# MCU.net
KiCad netlist of a schematic drawn in Altium Designer
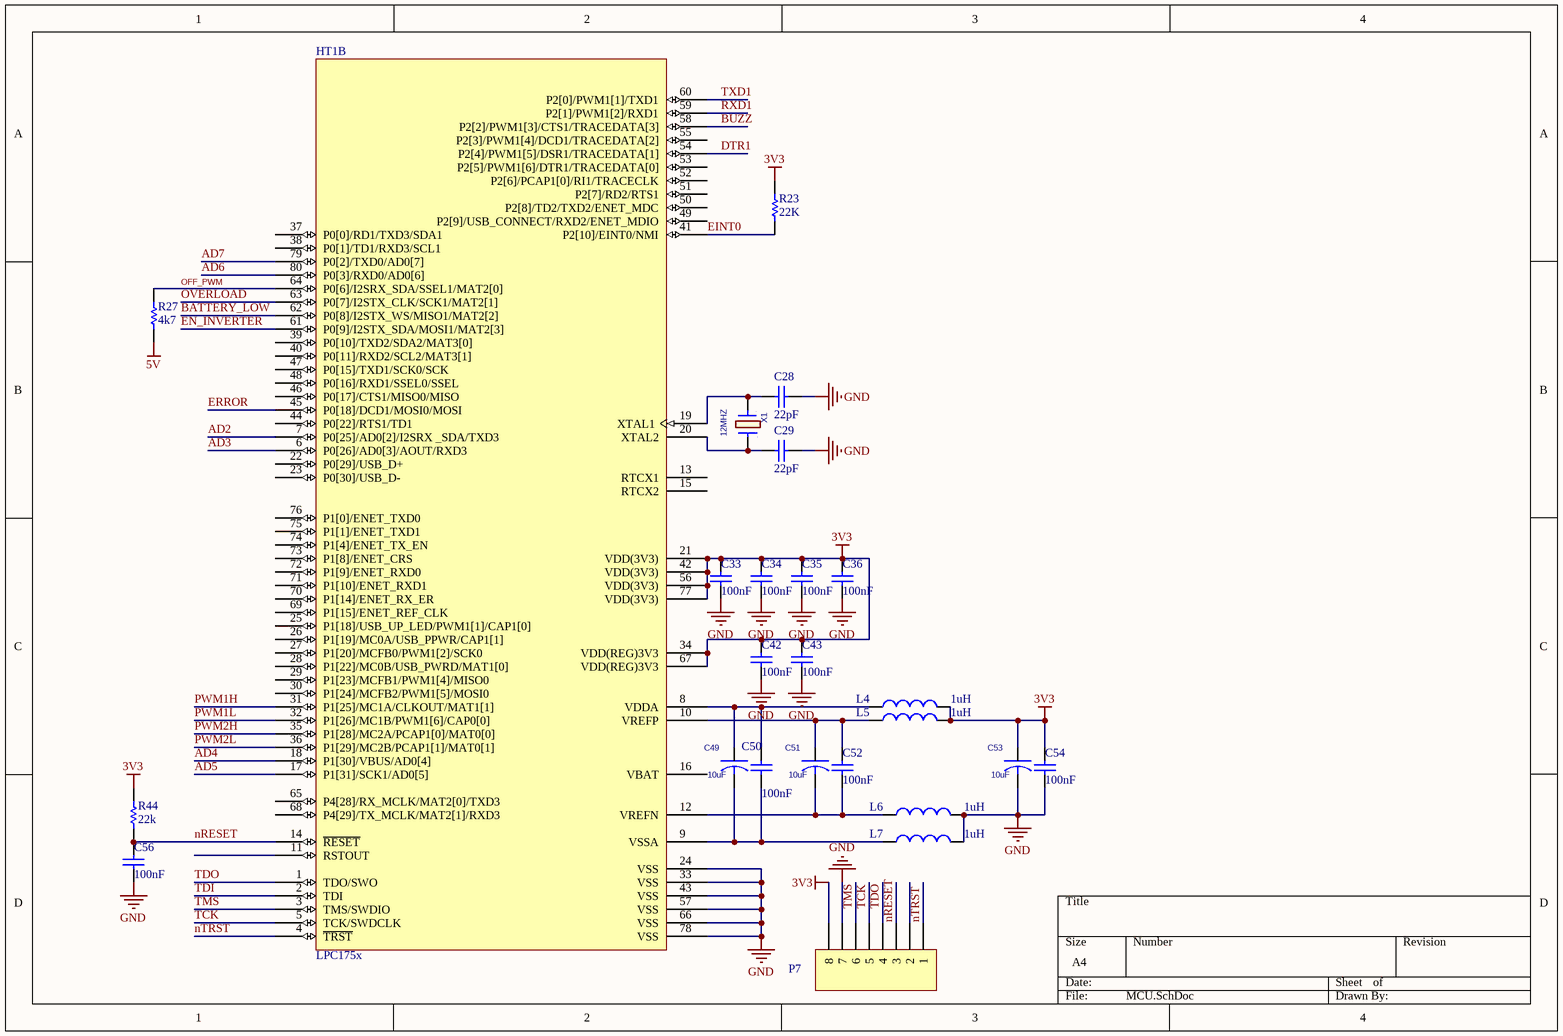
[diagram p0: MCU.SchDoc]

(export (version "E")
  (design (tool "Eeschema 10.0.6"))
  (components
    (comp (ref "C28")
      (value "22pF")
      (footprint "C0805")
      (description "Capacitor Type 0805 SMD")
      (fields (field (name "Comment") "CX4") (field (name "PUBLISHER") "Altium Limited"))
      (libsource (lib "Miscellaneous Devices") (part "Cap"))
    )
    (comp (ref "C29")
      (value "22pF")
      (footprint "C0805")
      (description "Capacitor Type 0805 SMD")
      (fields (field (name "Comment") "CX4") (field (name "PUBLISHER") "Altium Limited"))
      (libsource (lib "Miscellaneous Devices") (part "Cap"))
    )
    (comp (ref "C33")
      (value "100nF")
      (footprint "C0805")
      (description "Capacitor Type 0805 SMD")
      (fields (field (name "Comment") "CX4") (field (name "PUBLISHER") "Altium Limited"))
      (libsource (lib "Miscellaneous Devices") (part "Cap"))
    )
    (comp (ref "C34")
      (value "100nF")
      (footprint "C0805")
      (description "Capacitor Type 0805 SMD")
      (fields (field (name "Comment") "CX4") (field (name "PUBLISHER") "Altium Limited"))
      (libsource (lib "Miscellaneous Devices") (part "Cap"))
    )
    (comp (ref "C35")
      (value "100nF")
      (footprint "C0805")
      (description "Capacitor Type 0805 SMD")
      (fields (field (name "Comment") "CX4") (field (name "PUBLISHER") "Altium Limited"))
      (libsource (lib "Miscellaneous Devices") (part "Cap"))
    )
    (comp (ref "C36")
      (value "100nF")
      (footprint "C0805")
      (description "Capacitor Type 0805 SMD")
      (fields (field (name "Comment") "CX4") (field (name "PUBLISHER") "Altium Limited"))
      (libsource (lib "Miscellaneous Devices") (part "Cap"))
    )
    (comp (ref "C42")
      (value "100nF")
      (footprint "C0805")
      (description "Capacitor Type 0805 SMD")
      (fields (field (name "Comment") "CX4") (field (name "PUBLISHER") "Altium Limited"))
      (libsource (lib "Miscellaneous Devices") (part "Cap"))
    )
    (comp (ref "C43")
      (value "100nF")
      (footprint "C0805")
      (description "Capacitor Type 0805 SMD")
      (fields (field (name "Comment") "CX4") (field (name "PUBLISHER") "Altium Limited"))
      (libsource (lib "Miscellaneous Devices") (part "Cap"))
    )
    (comp (ref "C49") (value "10uF") (footprint "CAP_10uF_SMD") (libsource (lib "*") (part "C")))
    (comp (ref "C50")
      (value "100nF")
      (footprint "C0805")
      (description "Capacitor Type 0805 SMD")
      (fields (field (name "Comment") "CX4") (field (name "PUBLISHER") "Altium Limited"))
      (libsource (lib "Miscellaneous Devices") (part "Cap"))
    )
    (comp (ref "C51") (value "10uF") (footprint "CAP_10uF_SMD") (libsource (lib "*") (part "C")))
    (comp (ref "C52")
      (value "100nF")
      (footprint "C0805")
      (description "Capacitor Type 0805 SMD")
      (fields (field (name "Comment") "CX4") (field (name "PUBLISHER") "Altium Limited"))
      (libsource (lib "Miscellaneous Devices") (part "Cap"))
    )
    (comp (ref "C53") (value "10uF") (footprint "CAP_10uF_SMD") (libsource (lib "*") (part "C")))
    (comp (ref "C54")
      (value "100nF")
      (footprint "C0805")
      (description "Capacitor Type 0805 SMD")
      (fields (field (name "Comment") "CX4") (field (name "PUBLISHER") "Altium Limited"))
      (libsource (lib "Miscellaneous Devices") (part "Cap"))
    )
    (comp (ref "C56")
      (value "100nF")
      (footprint "C0805")
      (description "Capacitor Type 0805 SMD")
      (fields (field (name "Comment") "CX4") (field (name "PUBLISHER") "Altium Limited"))
      (libsource (lib "Miscellaneous Devices") (part "Cap"))
    )
    (comp (ref "HT1")
      (value "LPC175x")
      (footprint "PCBComponent_1 - duplicate")
      (libsource (lib "LPC175x") (part "LPC175x"))
    )
    (comp (ref "L4")
      (value "1uH")
      (footprint "L_1uH")
      (description "Inductor Type 1206 SMD")
      (fields (field (name "Comment") "Inductor") (field (name "PUBLISHER") "Altium Limited"))
      (libsource (lib "Miscellaneous Devices") (part "Inductor"))
    )
    (comp (ref "L5")
      (value "1uH")
      (footprint "L_1uH")
      (description "Inductor Type 1206 SMD")
      (fields (field (name "Comment") "Inductor") (field (name "PUBLISHER") "Altium Limited"))
      (libsource (lib "Miscellaneous Devices") (part "Inductor"))
    )
    (comp (ref "L6")
      (value "1uH")
      (footprint "L_1uH")
      (description "Inductor Type 1206 SMD")
      (fields (field (name "Comment") "Inductor") (field (name "PUBLISHER") "Altium Limited"))
      (libsource (lib "Miscellaneous Devices") (part "Inductor"))
    )
    (comp (ref "L7")
      (value "1uH")
      (footprint "L_1uH")
      (description "Inductor Type 1206 SMD")
      (fields (field (name "Comment") "Inductor") (field (name "PUBLISHER") "Altium Limited"))
      (libsource (lib "Miscellaneous Devices") (part "Inductor"))
    )
    (comp (ref "P7")
      (value "Header 8")
      (footprint "HDR1X8")
      (description "Header, 8-Pin")
      (fields (field (name "PUBLISHER") "Altium Limited"))
      (libsource (lib "Miscellaneous Connectors") (part "Header 8"))
    )
    (comp (ref "R23")
      (value "22K")
      (footprint "R0805")
      (description "Resistor SMD0805")
      (fields (field (name "PUBLISHER") "Altium Limited"))
      (libsource (lib "Miscellaneous Devices") (part "Res1"))
    )
    (comp (ref "R27")
      (value "4k7")
      (footprint "R0805")
      (description "Resistor SMD0805")
      (fields (field (name "PUBLISHER") "Altium Limited"))
      (libsource (lib "Miscellaneous Devices") (part "Res1"))
    )
    (comp (ref "R44")
      (value "22k")
      (footprint "R0805")
      (description "Resistor SMD0805")
      (fields (field (name "PUBLISHER") "Altium Limited"))
      (libsource (lib "Miscellaneous Devices") (part "Res1"))
    )
    (comp (ref "X1")
      (value "12MHZ")
      (footprint "CRYSTAL_12Mhz")
      (description "Thach anh 12MHZ")
      (libsource (lib "*") (part "QZS10MEG_0"))
    )
  )
  (nets
    (net (code "1") (name "/AD2") (class "Default")
      (node (ref "HT1") (pin "7") (pinfunction "P0[25]/AD0[2]/I2SRX__SDA/TXD3_7") (pintype "bidirectional"))
    )
    (net (code "2") (name "/AD3") (class "Default")
      (node (ref "HT1") (pin "6") (pinfunction "P0[26]/AD0[3]/AOUT/RXD3_6") (pintype "bidirectional"))
    )
    (net (code "3") (name "/AD4") (class "Default")
      (node (ref "HT1") (pin "18") (pinfunction "P1[30]/VBUS/AD0[4]_18") (pintype "bidirectional"))
    )
    (net (code "4") (name "/AD5") (class "Default")
      (node (ref "HT1") (pin "17") (pinfunction "P1[31]/SCK1/AD0[5]_17") (pintype "bidirectional"))
    )
    (net (code "5") (name "/AD6") (class "Default")
      (node (ref "HT1") (pin "80") (pinfunction "P0[3]/RXD0/AD0[6]_80") (pintype "bidirectional"))
    )
    (net (code "6") (name "/AD7") (class "Default")
      (node (ref "HT1") (pin "79") (pinfunction "P0[2]/TXD0/AD0[7]_79") (pintype "bidirectional"))
    )
    (net (code "7") (name "/BATTERY_LOW") (class "Default")
      (node (ref "HT1") (pin "62") (pinfunction "P0[8]/I2STX_WS/MISO1/MAT2[2]_62") (pintype "bidirectional"))
    )
    (net (code "8") (name "/BUZZ") (class "Default")
      (node (ref "HT1") (pin "58") (pinfunction "P2[2]/PWM1[3]/CTS1/TRACEDATA[3]_58") (pintype "bidirectional"))
    )
    (net (code "9") (name "/DTR1") (class "Default")
      (node (ref "HT1") (pin "54") (pinfunction "P2[4]/PWM1[5]/DSR1/TRACEDATA[1]_54") (pintype "bidirectional"))
    )
    (net (code "10") (name "/EINT0") (class "Default")
      (node (ref "HT1") (pin "41") (pinfunction "P2[10]/EINT0/NMI_41") (pintype "bidirectional"))
      (node (ref "R23") (pin "1") (pinfunction "1_1") (pintype "passive"))
    )
    (net (code "11") (name "/EN_INVERTER") (class "Default")
      (node (ref "HT1") (pin "61") (pinfunction "P0[9]/I2STX_SDA/MOSI1/MAT2[3]_61") (pintype "bidirectional"))
    )
    (net (code "12") (name "/ERROR") (class "Default")
      (node (ref "HT1") (pin "45") (pinfunction "P0[18]/DCD1/MOSI0/MOSI_45") (pintype "bidirectional"))
    )
    (net (code "13") (name "/OFF_PWM") (class "Default")
      (node (ref "HT1") (pin "64") (pinfunction "P0[6]/I2SRX_SDA/SSEL1/MAT2[0]_64") (pintype "bidirectional"))
      (node (ref "R27") (pin "2") (pinfunction "2_2") (pintype "passive"))
    )
    (net (code "14") (name "/OVERLOAD") (class "Default")
      (node (ref "HT1") (pin "63") (pinfunction "P0[7]/I2STX_CLK/SCK1/MAT2[1]_63") (pintype "bidirectional"))
    )
    (net (code "15") (name "/PWM1H") (class "Default")
      (node (ref "HT1") (pin "31") (pinfunction "P1[25]/MC1A/CLKOUT/MAT1[1]_31") (pintype "bidirectional"))
    )
    (net (code "16") (name "/PWM1L") (class "Default")
      (node (ref "HT1") (pin "32") (pinfunction "P1[26]/MC1B/PWM1[6]/CAP0[0]_32") (pintype "bidirectional"))
    )
    (net (code "17") (name "/PWM2H") (class "Default")
      (node (ref "HT1") (pin "35") (pinfunction "P1[28]/MC2A/PCAP1[0]/MAT0[0]_35") (pintype "bidirectional"))
    )
    (net (code "18") (name "/PWM2L") (class "Default")
      (node (ref "HT1") (pin "36") (pinfunction "P1[29]/MC2B/PCAP1[1]/MAT0[1]_36") (pintype "bidirectional"))
    )
    (net (code "19") (name "/RXD1") (class "Default")
      (node (ref "HT1") (pin "59") (pinfunction "P2[1]/PWM1[2]/RXD1_59") (pintype "bidirectional"))
    )
    (net (code "20") (name "/TCK") (class "Default")
      (node (ref "HT1") (pin "5") (pinfunction "TCK/SWDCLK_5") (pintype "bidirectional"))
      (node (ref "P7") (pin "5") (pinfunction "5_5") (pintype "passive"))
    )
    (net (code "21") (name "/TDI") (class "Default")
      (node (ref "HT1") (pin "2") (pinfunction "TDI_2") (pintype "bidirectional"))
    )
    (net (code "22") (name "/TDO") (class "Default")
      (node (ref "HT1") (pin "1") (pinfunction "TDO/SWO_1") (pintype "bidirectional"))
      (node (ref "P7") (pin "4") (pinfunction "4_4") (pintype "passive"))
    )
    (net (code "23") (name "/TMS") (class "Default")
      (node (ref "HT1") (pin "3") (pinfunction "TMS/SWDIO_3") (pintype "bidirectional"))
      (node (ref "P7") (pin "6") (pinfunction "6_6") (pintype "passive"))
    )
    (net (code "24") (name "/TXD1") (class "Default")
      (node (ref "HT1") (pin "60") (pinfunction "P2[0]/PWM1[1]/TXD1_60") (pintype "bidirectional"))
    )
    (net (code "25") (name "/nRESET") (class "Default")
      (node (ref "C56") (pin "2") (pinfunction "2_2") (pintype "passive"))
      (node (ref "HT1") (pin "14") (pinfunction "~{RESET}_14") (pintype "bidirectional"))
      (node (ref "P7") (pin "3") (pinfunction "3_3") (pintype "passive"))
      (node (ref "R44") (pin "1") (pinfunction "1_1") (pintype "passive"))
    )
    (net (code "26") (name "/nTRST") (class "Default")
      (node (ref "HT1") (pin "4") (pinfunction "~{TRST}_4") (pintype "bidirectional"))
      (node (ref "P7") (pin "1") (pinfunction "1_1") (pintype "passive"))
    )
    (net (code "27") (name "3V3") (class "Default")
      (node (ref "C33") (pin "2") (pinfunction "2_2") (pintype "passive"))
      (node (ref "C34") (pin "2") (pinfunction "2_2") (pintype "passive"))
      (node (ref "C35") (pin "2") (pinfunction "2_2") (pintype "passive"))
      (node (ref "C36") (pin "2") (pinfunction "2_2") (pintype "passive"))
      (node (ref "C42") (pin "2") (pinfunction "2_2") (pintype "passive"))
      (node (ref "C43") (pin "2") (pinfunction "2_2") (pintype "passive"))
      (node (ref "C53") (pin "1") (pinfunction "1_1") (pintype "passive"))
      (node (ref "C54") (pin "2") (pinfunction "2_2") (pintype "passive"))
      (node (ref "HT1") (pin "21") (pinfunction "VDD(3V3)_21") (pintype "power_in"))
      (node (ref "HT1") (pin "34") (pinfunction "VDD(REG)3V3_34") (pintype "power_in"))
      (node (ref "HT1") (pin "42") (pinfunction "VDD(3V3)_42") (pintype "power_in"))
      (node (ref "HT1") (pin "56") (pinfunction "VDD(3V3)_56") (pintype "power_in"))
      (node (ref "HT1") (pin "67") (pinfunction "VDD(REG)3V3_67") (pintype "power_in"))
      (node (ref "HT1") (pin "77") (pinfunction "VDD(3V3)_77") (pintype "power_in"))
      (node (ref "L4") (pin "2") (pinfunction "2_2") (pintype "passive"))
      (node (ref "L5") (pin "2") (pinfunction "2_2") (pintype "passive"))
      (node (ref "P7") (pin "8") (pinfunction "8_8") (pintype "passive"))
      (node (ref "R23") (pin "2") (pinfunction "2_2") (pintype "passive"))
      (node (ref "R44") (pin "2") (pinfunction "2_2") (pintype "passive"))
    )
    (net (code "28") (name "5V") (class "Default")
      (node (ref "R27") (pin "1") (pinfunction "1_1") (pintype "passive"))
    )
    (net (code "29") (name "GND") (class "Default")
      (node (ref "C28") (pin "1") (pinfunction "1_1") (pintype "passive"))
      (node (ref "C29") (pin "1") (pinfunction "1_1") (pintype "passive"))
      (node (ref "C33") (pin "1") (pinfunction "1_1") (pintype "passive"))
      (node (ref "C34") (pin "1") (pinfunction "1_1") (pintype "passive"))
      (node (ref "C35") (pin "1") (pinfunction "1_1") (pintype "passive"))
      (node (ref "C36") (pin "1") (pinfunction "1_1") (pintype "passive"))
      (node (ref "C42") (pin "1") (pinfunction "1_1") (pintype "passive"))
      (node (ref "C43") (pin "1") (pinfunction "1_1") (pintype "passive"))
      (node (ref "C53") (pin "2") (pinfunction "2_2") (pintype "passive"))
      (node (ref "C54") (pin "1") (pinfunction "1_1") (pintype "passive"))
      (node (ref "C56") (pin "1") (pinfunction "1_1") (pintype "passive"))
      (node (ref "HT1") (pin "24") (pinfunction "VSS_24") (pintype "power_in"))
      (node (ref "HT1") (pin "33") (pinfunction "VSS_33") (pintype "power_in"))
      (node (ref "HT1") (pin "43") (pinfunction "VSS_43") (pintype "power_in"))
      (node (ref "HT1") (pin "57") (pinfunction "VSS_57") (pintype "power_in"))
      (node (ref "HT1") (pin "66") (pinfunction "VSS_66") (pintype "power_in"))
      (node (ref "HT1") (pin "78") (pinfunction "VSS_78") (pintype "power_in"))
      (node (ref "L6") (pin "2") (pinfunction "2_2") (pintype "passive"))
      (node (ref "L7") (pin "2") (pinfunction "2_2") (pintype "passive"))
      (node (ref "P7") (pin "7") (pinfunction "7_7") (pintype "passive"))
    )
    (net (code "30") (name "Net-(HT1B-VDDA)") (class "Default")
      (node (ref "C49") (pin "1") (pinfunction "1_1") (pintype "passive"))
      (node (ref "C50") (pin "2") (pinfunction "2_2") (pintype "passive"))
      (node (ref "HT1") (pin "8") (pinfunction "VDDA_8") (pintype "power_in"))
      (node (ref "L4") (pin "1") (pinfunction "1_1") (pintype "passive"))
    )
    (net (code "31") (name "Net-(HT1B-VREFN)") (class "Default")
      (node (ref "C51") (pin "2") (pinfunction "2_2") (pintype "passive"))
      (node (ref "C52") (pin "1") (pinfunction "1_1") (pintype "passive"))
      (node (ref "HT1") (pin "12") (pinfunction "VREFN_12") (pintype "power_in"))
      (node (ref "L6") (pin "1") (pinfunction "1_1") (pintype "passive"))
    )
    (net (code "32") (name "Net-(HT1B-VREFP)") (class "Default")
      (node (ref "C51") (pin "1") (pinfunction "1_1") (pintype "passive"))
      (node (ref "C52") (pin "2") (pinfunction "2_2") (pintype "passive"))
      (node (ref "HT1") (pin "10") (pinfunction "VREFP_10") (pintype "power_in"))
      (node (ref "L5") (pin "1") (pinfunction "1_1") (pintype "passive"))
    )
    (net (code "33") (name "Net-(HT1B-VSSA)") (class "Default")
      (node (ref "C49") (pin "2") (pinfunction "2_2") (pintype "passive"))
      (node (ref "C50") (pin "1") (pinfunction "1_1") (pintype "passive"))
      (node (ref "HT1") (pin "9") (pinfunction "VSSA_9") (pintype "power_in"))
      (node (ref "L7") (pin "1") (pinfunction "1_1") (pintype "passive"))
    )
    (net (code "34") (name "Net-(HT1B-XTAL1)") (class "Default")
      (node (ref "C28") (pin "2") (pinfunction "2_2") (pintype "passive"))
      (node (ref "HT1") (pin "19") (pinfunction "XTAL1_19") (pintype "input"))
      (node (ref "X1") (pin "1") (pinfunction "1_1") (pintype "passive"))
    )
    (net (code "35") (name "Net-(HT1B-XTAL2)") (class "Default")
      (node (ref "C29") (pin "2") (pinfunction "2_2") (pintype "passive"))
      (node (ref "HT1") (pin "20") (pinfunction "XTAL2_20") (pintype "passive"))
      (node (ref "X1") (pin "2") (pinfunction "2_2") (pintype "passive"))
    )
    (net (code "36") (name "unconnected-(HT1B-P0[0]{slash}RD1{slash}TXD3{slash}SDA1-Pad37)") (class "Default")
      (node (ref "HT1") (pin "37") (pinfunction "P0[0]/RD1/TXD3/SDA1_37") (pintype "bidirectional"))
    )
    (net (code "37") (name "unconnected-(HT1B-P0[1]{slash}TD1{slash}RXD3{slash}SCL1-Pad38)") (class "Default")
      (node (ref "HT1") (pin "38") (pinfunction "P0[1]/TD1/RXD3/SCL1_38") (pintype "bidirectional"))
    )
    (net (code "38") (name "unconnected-(HT1B-P0[10]{slash}TXD2{slash}SDA2{slash}MAT3[0]-Pad39)") (class "Default")
      (node (ref "HT1") (pin "39") (pinfunction "P0[10]/TXD2/SDA2/MAT3[0]_39") (pintype "bidirectional"))
    )
    (net (code "39") (name "unconnected-(HT1B-P0[11]{slash}RXD2{slash}SCL2{slash}MAT3[1]-Pad40)") (class "Default")
      (node (ref "HT1") (pin "40") (pinfunction "P0[11]/RXD2/SCL2/MAT3[1]_40") (pintype "bidirectional"))
    )
    (net (code "40") (name "unconnected-(HT1B-P0[15]{slash}TXD1{slash}SCK0{slash}SCK-Pad47)") (class "Default")
      (node (ref "HT1") (pin "47") (pinfunction "P0[15]/TXD1/SCK0/SCK_47") (pintype "bidirectional"))
    )
    (net (code "41") (name "unconnected-(HT1B-P0[16]{slash}RXD1{slash}SSEL0{slash}SSEL-Pad48)") (class "Default")
      (node (ref "HT1") (pin "48") (pinfunction "P0[16]/RXD1/SSEL0/SSEL_48") (pintype "bidirectional"))
    )
    (net (code "42") (name "unconnected-(HT1B-P0[17]{slash}CTS1{slash}MISO0{slash}MISO-Pad46)") (class "Default")
      (node (ref "HT1") (pin "46") (pinfunction "P0[17]/CTS1/MISO0/MISO_46") (pintype "bidirectional"))
    )
    (net (code "43") (name "unconnected-(HT1B-P0[22]{slash}RTS1{slash}TD1-Pad44)") (class "Default")
      (node (ref "HT1") (pin "44") (pinfunction "P0[22]/RTS1/TD1_44") (pintype "bidirectional"))
    )
    (net (code "44") (name "unconnected-(HT1B-P0[29]{slash}USB_D+-Pad22)") (class "Default")
      (node (ref "HT1") (pin "22") (pinfunction "P0[29]/USB_D+_22") (pintype "bidirectional"))
    )
    (net (code "45") (name "unconnected-(HT1B-P0[30]{slash}USB_D--Pad23)") (class "Default")
      (node (ref "HT1") (pin "23") (pinfunction "P0[30]/USB_D-_23") (pintype "bidirectional"))
    )
    (net (code "46") (name "unconnected-(HT1B-P1[0]{slash}ENET_TXD0-Pad76)") (class "Default")
      (node (ref "HT1") (pin "76") (pinfunction "P1[0]/ENET_TXD0_76") (pintype "bidirectional"))
    )
    (net (code "47") (name "unconnected-(HT1B-P1[1]{slash}ENET_TXD1-Pad75)") (class "Default")
      (node (ref "HT1") (pin "75") (pinfunction "P1[1]/ENET_TXD1_75") (pintype "bidirectional"))
    )
    (net (code "48") (name "unconnected-(HT1B-P1[4]{slash}ENET_TX_EN-Pad74)") (class "Default")
      (node (ref "HT1") (pin "74") (pinfunction "P1[4]/ENET_TX_EN_74") (pintype "bidirectional"))
    )
    (net (code "49") (name "unconnected-(HT1B-P1[8]{slash}ENET_CRS-Pad73)") (class "Default")
      (node (ref "HT1") (pin "73") (pinfunction "P1[8]/ENET_CRS_73") (pintype "bidirectional"))
    )
    (net (code "50") (name "unconnected-(HT1B-P1[9]{slash}ENET_RXD0-Pad72)") (class "Default")
      (node (ref "HT1") (pin "72") (pinfunction "P1[9]/ENET_RXD0_72") (pintype "bidirectional"))
    )
    (net (code "51") (name "unconnected-(HT1B-P1[10]{slash}ENET_RXD1-Pad71)") (class "Default")
      (node (ref "HT1") (pin "71") (pinfunction "P1[10]/ENET_RXD1_71") (pintype "bidirectional"))
    )
    (net (code "52") (name "unconnected-(HT1B-P1[14]{slash}ENET_RX_ER-Pad70)") (class "Default")
      (node (ref "HT1") (pin "70") (pinfunction "P1[14]/ENET_RX_ER_70") (pintype "bidirectional"))
    )
    (net (code "53") (name "unconnected-(HT1B-P1[15]{slash}ENET_REF_CLK-Pad69)") (class "Default")
      (node (ref "HT1") (pin "69") (pinfunction "P1[15]/ENET_REF_CLK_69") (pintype "bidirectional"))
    )
    (net (code "54") (name "unconnected-(HT1B-P1[18]{slash}USB_UP_LED{slash}PWM1[1]{slash}CAP1[0]-Pad25)") (class "Default")
      (node (ref "HT1") (pin "25") (pinfunction "P1[18]/USB_UP_LED/PWM1[1]/CAP1[0]_25") (pintype "bidirectional"))
    )
    (net (code "55") (name "unconnected-(HT1B-P1[19]{slash}MC0A{slash}USB_PPWR{slash}CAP1[1]-Pad26)") (class "Default")
      (node (ref "HT1") (pin "26") (pinfunction "P1[19]/MC0A/USB_PPWR/CAP1[1]_26") (pintype "bidirectional"))
    )
    (net (code "56") (name "unconnected-(HT1B-P1[20]{slash}MCFB0{slash}PWM1[2]{slash}SCK0-Pad27)") (class "Default")
      (node (ref "HT1") (pin "27") (pinfunction "P1[20]/MCFB0/PWM1[2]/SCK0_27") (pintype "bidirectional"))
    )
    (net (code "57") (name "unconnected-(HT1B-P1[22]{slash}MC0B{slash}USB_PWRD{slash}MAT1[0]-Pad28)") (class "Default")
      (node (ref "HT1") (pin "28") (pinfunction "P1[22]/MC0B/USB_PWRD/MAT1[0]_28") (pintype "bidirectional"))
    )
    (net (code "58") (name "unconnected-(HT1B-P1[23]{slash}MCFB1{slash}PWM1[4]{slash}MISO0-Pad29)") (class "Default")
      (node (ref "HT1") (pin "29") (pinfunction "P1[23]/MCFB1/PWM1[4]/MISO0_29") (pintype "bidirectional"))
    )
    (net (code "59") (name "unconnected-(HT1B-P1[24]{slash}MCFB2{slash}PWM1[5]{slash}MOSI0-Pad30)") (class "Default")
      (node (ref "HT1") (pin "30") (pinfunction "P1[24]/MCFB2/PWM1[5]/MOSI0_30") (pintype "bidirectional"))
    )
    (net (code "60") (name "unconnected-(HT1B-P2[3]{slash}PWM1[4]{slash}DCD1{slash}TRACEDATA[2]-Pad55)") (class "Default")
      (node (ref "HT1") (pin "55") (pinfunction "P2[3]/PWM1[4]/DCD1/TRACEDATA[2]_55") (pintype "bidirectional"))
    )
    (net (code "61") (name "unconnected-(HT1B-P2[5]{slash}PWM1[6]{slash}DTR1{slash}TRACEDATA[0]-Pad53)") (class "Default")
      (node (ref "HT1") (pin "53") (pinfunction "P2[5]/PWM1[6]/DTR1/TRACEDATA[0]_53") (pintype "bidirectional"))
    )
    (net (code "62") (name "unconnected-(HT1B-P2[6]{slash}PCAP1[0]{slash}RI1{slash}TRACECLK-Pad52)") (class "Default")
      (node (ref "HT1") (pin "52") (pinfunction "P2[6]/PCAP1[0]/RI1/TRACECLK_52") (pintype "bidirectional"))
    )
    (net (code "63") (name "unconnected-(HT1B-P2[7]{slash}RD2{slash}RTS1-Pad51)") (class "Default")
      (node (ref "HT1") (pin "51") (pinfunction "P2[7]/RD2/RTS1_51") (pintype "bidirectional"))
    )
    (net (code "64") (name "unconnected-(HT1B-P2[8]{slash}TD2{slash}TXD2{slash}ENET_MDC-Pad50)") (class "Default")
      (node (ref "HT1") (pin "50") (pinfunction "P2[8]/TD2/TXD2/ENET_MDC_50") (pintype "bidirectional"))
    )
    (net (code "65") (name "unconnected-(HT1B-P2[9]{slash}USB_CONNECT{slash}RXD2{slash}ENET_MDIO-Pad49)") (class "Default")
      (node (ref "HT1") (pin "49") (pinfunction "P2[9]/USB_CONNECT/RXD2/ENET_MDIO_49") (pintype "bidirectional"))
    )
    (net (code "66") (name "unconnected-(HT1B-P4[28]{slash}RX_MCLK{slash}MAT2[0]{slash}TXD3-Pad65)") (class "Default")
      (node (ref "HT1") (pin "65") (pinfunction "P4[28]/RX_MCLK/MAT2[0]/TXD3_65") (pintype "bidirectional"))
    )
    (net (code "67") (name "unconnected-(HT1B-P4[29]{slash}TX_MCLK{slash}MAT2[1]{slash}RXD3-Pad68)") (class "Default")
      (node (ref "HT1") (pin "68") (pinfunction "P4[29]/TX_MCLK/MAT2[1]/RXD3_68") (pintype "bidirectional"))
    )
    (net (code "68") (name "unconnected-(HT1B-RSTOUT-Pad11)") (class "Default")
      (node (ref "HT1") (pin "11") (pinfunction "RSTOUT_11") (pintype "bidirectional"))
    )
    (net (code "69") (name "unconnected-(HT1B-RTCX1-Pad13)") (class "Default")
      (node (ref "HT1") (pin "13") (pinfunction "RTCX1_13") (pintype "passive"))
    )
    (net (code "70") (name "unconnected-(HT1B-RTCX2-Pad15)") (class "Default")
      (node (ref "HT1") (pin "15") (pinfunction "RTCX2_15") (pintype "passive"))
    )
    (net (code "71") (name "unconnected-(HT1B-VBAT-Pad16)") (class "Default")
      (node (ref "HT1") (pin "16") (pinfunction "VBAT_16") (pintype "power_in"))
    )
    (net (code "72") (name "unconnected-(P7-Pad2)") (class "Default")
      (node (ref "P7") (pin "2") (pinfunction "2_2") (pintype "passive"))
    )
  )
)
